# s2k_vr.net
KiCad netlist of a schematic drawn in EAGLE
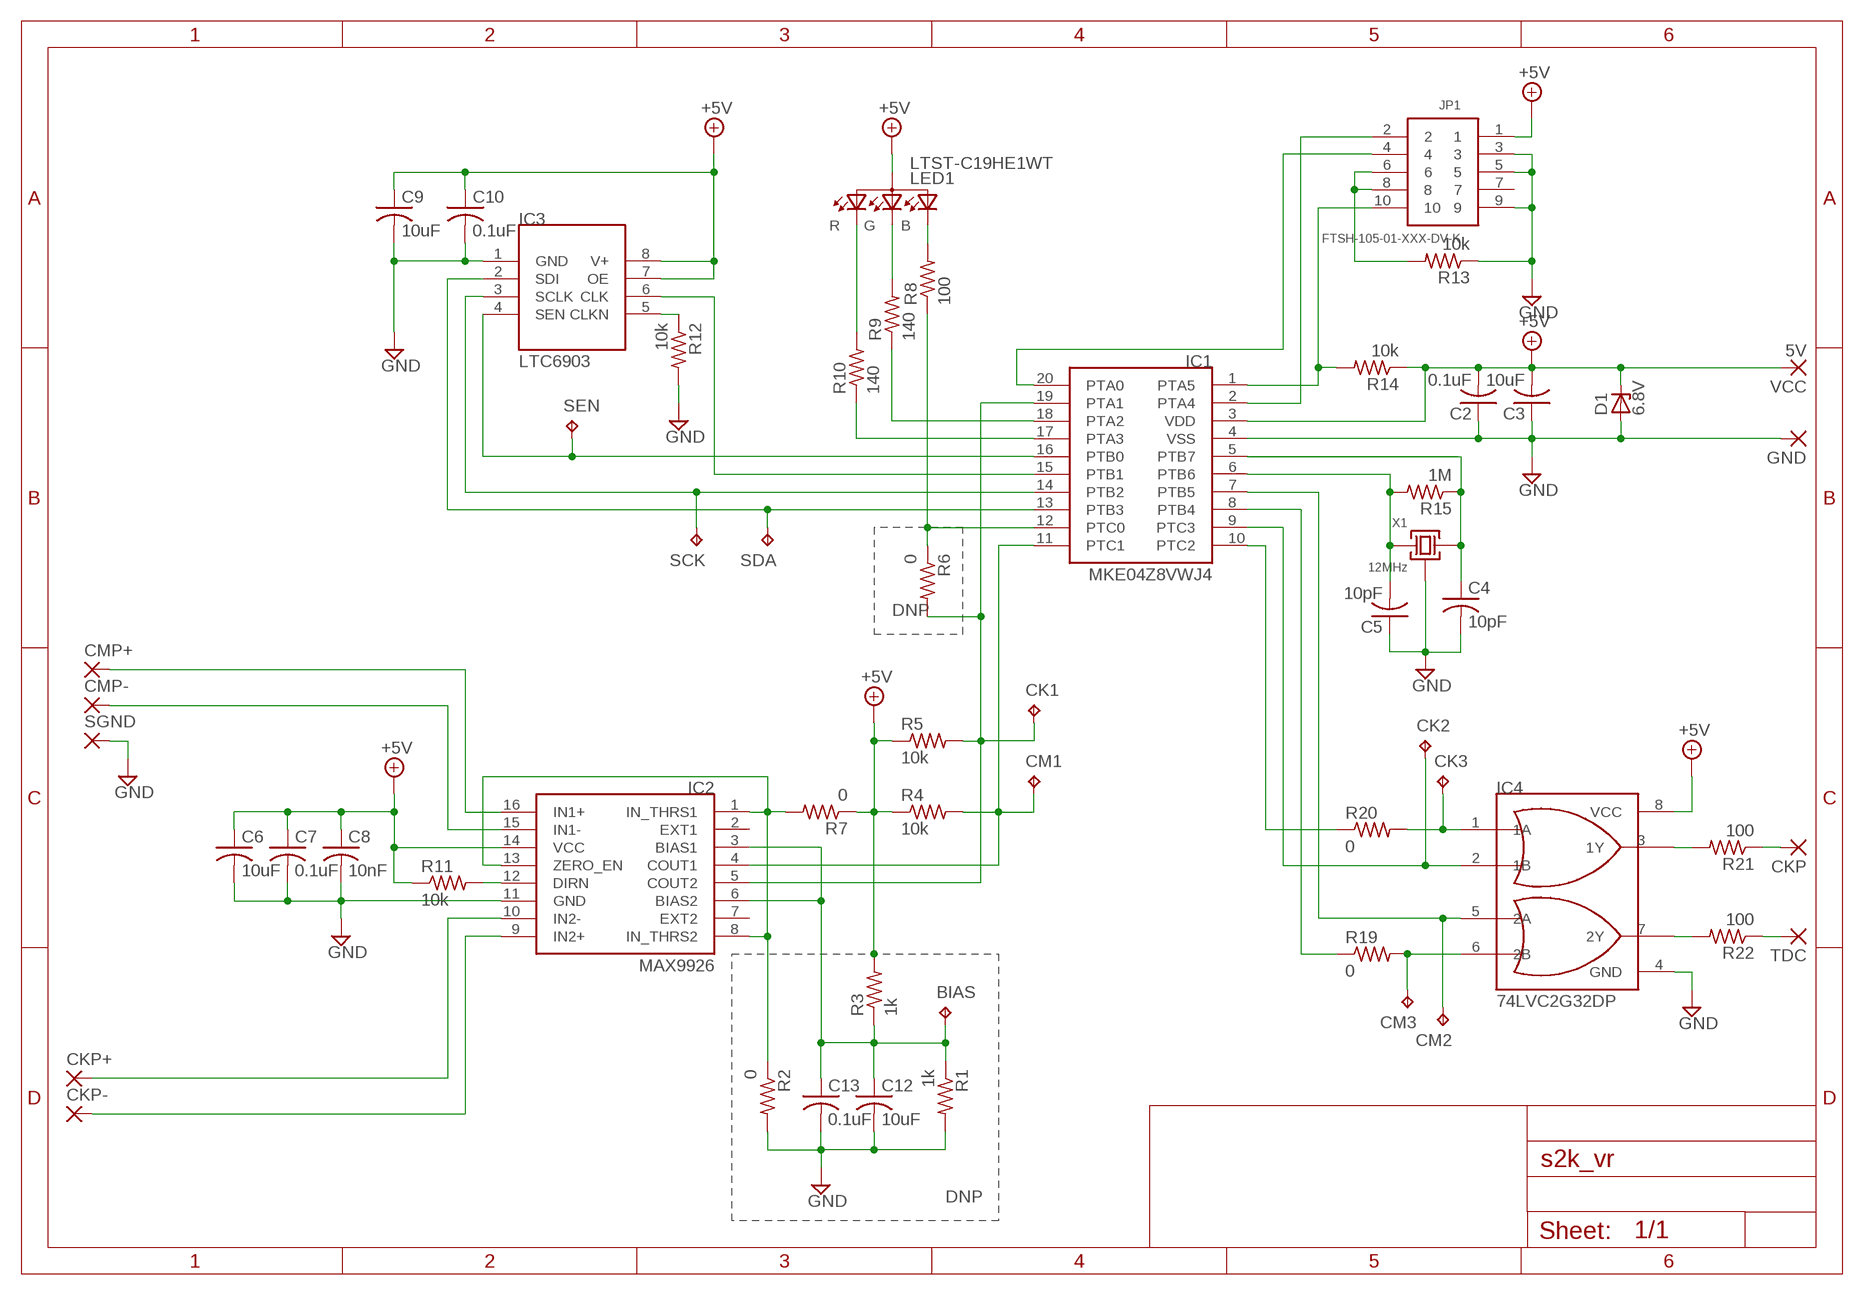
[diagram p0: schematic, sheet 1]

(export (version "E")
  (design (tool "Eeschema 10.0.6"))
  (components
    (comp (ref "BIAS")
      (value "TPB2,54")
      (footprint "eagle-import:B2,54")
      (libsource (lib "eagle-import") (part "TPB2,54"))
    )
    (comp (ref "C2")
      (value "0.1uF")
      (footprint "eagle-import:C0603")
      (libsource (lib "eagle-import") (part "C-USC0603"))
    )
    (comp (ref "C3")
      (value "10uF")
      (footprint "eagle-import:C0805")
      (libsource (lib "eagle-import") (part "C-USC0805"))
    )
    (comp (ref "C4")
      (value "10pF")
      (footprint "eagle-import:C0603")
      (libsource (lib "eagle-import") (part "C-USC0603"))
    )
    (comp (ref "C5")
      (value "10pF")
      (footprint "eagle-import:C0603")
      (libsource (lib "eagle-import") (part "C-USC0603"))
    )
    (comp (ref "C6")
      (value "10uF")
      (footprint "eagle-import:C0805")
      (libsource (lib "eagle-import") (part "C-USC0805"))
    )
    (comp (ref "C7")
      (value "0.1uF")
      (footprint "eagle-import:C0603")
      (libsource (lib "eagle-import") (part "C-USC0603"))
    )
    (comp (ref "C8")
      (value "10nF")
      (footprint "eagle-import:C0306")
      (libsource (lib "eagle-import") (part "CAP-0306"))
    )
    (comp (ref "C9")
      (value "10uF")
      (footprint "eagle-import:C0805")
      (libsource (lib "eagle-import") (part "C-USC0805"))
    )
    (comp (ref "C10")
      (value "0.1uF")
      (footprint "eagle-import:C0603")
      (libsource (lib "eagle-import") (part "C-USC0603"))
    )
    (comp (ref "C12")
      (value "10uF")
      (footprint "eagle-import:C0603")
      (libsource (lib "eagle-import") (part "C-USC0603"))
    )
    (comp (ref "C13")
      (value "0.1uF")
      (footprint "eagle-import:C0603")
      (libsource (lib "eagle-import") (part "C-USC0603"))
    )
    (comp (ref "CK1")
      (value "TPB2,54")
      (footprint "eagle-import:B2,54")
      (libsource (lib "eagle-import") (part "TPB2,54"))
    )
    (comp (ref "CK2")
      (value "TPB2,54")
      (footprint "eagle-import:B2,54")
      (libsource (lib "eagle-import") (part "TPB2,54"))
    )
    (comp (ref "CK3")
      (value "TPB2,54")
      (footprint "eagle-import:B2,54")
      (libsource (lib "eagle-import") (part "TPB2,54"))
    )
    (comp (ref "CKP")
      (value "3,81/1,4")
      (footprint "eagle-import:3,81_1,4")
      (libsource (lib "eagle-import") (part "3,81/1,4"))
    )
    (comp (ref "CKP+")
      (value "3,81/1,4")
      (footprint "eagle-import:3,81_1,4")
      (libsource (lib "eagle-import") (part "3,81/1,4"))
    )
    (comp (ref "CKP-")
      (value "3,81/1,4")
      (footprint "eagle-import:3,81_1,4")
      (libsource (lib "eagle-import") (part "3,81/1,4"))
    )
    (comp (ref "CM1")
      (value "TPB2,54")
      (footprint "eagle-import:B2,54")
      (libsource (lib "eagle-import") (part "TPB2,54"))
    )
    (comp (ref "CM2")
      (value "TPB2,54")
      (footprint "eagle-import:B2,54")
      (libsource (lib "eagle-import") (part "TPB2,54"))
    )
    (comp (ref "CM3")
      (value "TPB2,54")
      (footprint "eagle-import:B2,54")
      (libsource (lib "eagle-import") (part "TPB2,54"))
    )
    (comp (ref "CMP+")
      (value "3,81/1,4")
      (footprint "eagle-import:3,81_1,4")
      (libsource (lib "eagle-import") (part "3,81/1,4"))
    )
    (comp (ref "CMP-")
      (value "3,81/1,4")
      (footprint "eagle-import:3,81_1,4")
      (libsource (lib "eagle-import") (part "3,81/1,4"))
    )
    (comp (ref "D1")
      (value "6.8V")
      (footprint "eagle-import:SOT23")
      (libsource (lib "eagle-import") (part "ZENER-DIODESOT23"))
    )
    (comp (ref "GND")
      (value "3,81/1,4")
      (footprint "eagle-import:3,81_1,4")
      (libsource (lib "eagle-import") (part "3,81/1,4"))
    )
    (comp (ref "IC1")
      (value "MKE04Z8VWJ4")
      (footprint "eagle-import:SOIC20S")
      (libsource (lib "eagle-import") (part "MKE04Z8VWJ4"))
    )
    (comp (ref "IC2")
      (value "MAX9926")
      (footprint "eagle-import:16-QSOP")
      (libsource (lib "eagle-import") (part "MAX9926"))
    )
    (comp (ref "IC3")
      (value "LTC6903")
      (footprint "eagle-import:MS8")
      (libsource (lib "eagle-import") (part "LTC6903"))
    )
    (comp (ref "IC4")
      (value "74LVC2G32DP")
      (footprint "eagle-import:TSSOP8")
      (libsource (lib "eagle-import") (part "74LVC2G32DP"))
    )
    (comp (ref "JP1")
      (value "FTSH-105-01-XXX-DV-K")
      (footprint "eagle-import:FTSH-105-01-XXX-DV-K")
      (libsource (lib "eagle-import") (part "FTSH-105-01-XXX-DV-K"))
    )
    (comp (ref "LED1")
      (value "LTST-C19HE1WT")
      (footprint "eagle-import:LED-0606")
      (libsource (lib "eagle-import") (part "LTST-C19HE1WT"))
    )
    (comp (ref "R1")
      (value "1k")
      (footprint "eagle-import:R0603")
      (libsource (lib "eagle-import") (part "R-US_R0603"))
    )
    (comp (ref "R2")
      (value "0")
      (footprint "eagle-import:R0603")
      (libsource (lib "eagle-import") (part "R-US_R0603"))
    )
    (comp (ref "R3")
      (value "1k")
      (footprint "eagle-import:R0603")
      (libsource (lib "eagle-import") (part "R-US_R0603"))
    )
    (comp (ref "R4")
      (value "10k")
      (footprint "eagle-import:R0603")
      (libsource (lib "eagle-import") (part "R-US_R0603"))
    )
    (comp (ref "R5")
      (value "10k")
      (footprint "eagle-import:R0603")
      (libsource (lib "eagle-import") (part "R-US_R0603"))
    )
    (comp (ref "R6")
      (value "0")
      (footprint "eagle-import:R0603")
      (libsource (lib "eagle-import") (part "R-US_R0603"))
    )
    (comp (ref "R7")
      (value "0")
      (footprint "eagle-import:R0603")
      (libsource (lib "eagle-import") (part "R-US_R0603"))
    )
    (comp (ref "R8")
      (value "100")
      (footprint "eagle-import:R0603")
      (libsource (lib "eagle-import") (part "R-US_R0603"))
    )
    (comp (ref "R9")
      (value "140")
      (footprint "eagle-import:R0603")
      (libsource (lib "eagle-import") (part "R-US_R0603"))
    )
    (comp (ref "R10")
      (value "140")
      (footprint "eagle-import:R0603")
      (libsource (lib "eagle-import") (part "R-US_R0603"))
    )
    (comp (ref "R11")
      (value "10k")
      (footprint "eagle-import:R0603")
      (libsource (lib "eagle-import") (part "R-US_R0603"))
    )
    (comp (ref "R12")
      (value "10k")
      (footprint "eagle-import:R0603")
      (libsource (lib "eagle-import") (part "R-US_R0603"))
    )
    (comp (ref "R13")
      (value "10k")
      (footprint "eagle-import:R0603")
      (libsource (lib "eagle-import") (part "R-US_R0603"))
    )
    (comp (ref "R14")
      (value "10k")
      (footprint "eagle-import:R0603")
      (libsource (lib "eagle-import") (part "R-US_R0603"))
    )
    (comp (ref "R15")
      (value "1M")
      (footprint "eagle-import:R0603")
      (libsource (lib "eagle-import") (part "R-US_R0603"))
    )
    (comp (ref "R19")
      (value "0")
      (footprint "eagle-import:R0603")
      (libsource (lib "eagle-import") (part "R-US_R0603"))
    )
    (comp (ref "R20")
      (value "0")
      (footprint "eagle-import:R0603")
      (libsource (lib "eagle-import") (part "R-US_R0603"))
    )
    (comp (ref "R21")
      (value "100")
      (footprint "eagle-import:R0603")
      (libsource (lib "eagle-import") (part "R-US_R0603"))
    )
    (comp (ref "R22")
      (value "100")
      (footprint "eagle-import:R0603")
      (libsource (lib "eagle-import") (part "R-US_R0603"))
    )
    (comp (ref "SCK")
      (value "TPB2,54")
      (footprint "eagle-import:B2,54")
      (libsource (lib "eagle-import") (part "TPB2,54"))
    )
    (comp (ref "SDA")
      (value "TPB2,54")
      (footprint "eagle-import:B2,54")
      (libsource (lib "eagle-import") (part "TPB2,54"))
    )
    (comp (ref "SEN")
      (value "TPB2,54")
      (footprint "eagle-import:B2,54")
      (libsource (lib "eagle-import") (part "TPB2,54"))
    )
    (comp (ref "SGND")
      (value "3,81/1,4")
      (footprint "eagle-import:3,81_1,4")
      (libsource (lib "eagle-import") (part "3,81/1,4"))
    )
    (comp (ref "TDC")
      (value "3,81/1,4")
      (footprint "eagle-import:3,81_1,4")
      (libsource (lib "eagle-import") (part "3,81/1,4"))
    )
    (comp (ref "VCC")
      (value "5V")
      (footprint "eagle-import:3,81_1,4")
      (libsource (lib "eagle-import") (part "3,81/1,4"))
    )
    (comp (ref "X1")
      (value "12MHz")
      (footprint "eagle-import:SMD4-2520")
      (libsource (lib "eagle-import") (part "CX2520DB"))
    )
  )
  (nets
    (net (code "1") (name "+5V") (class "Default")
      (node (ref "C10") (pin "1") (pinfunction "1_1") (pintype "passive"))
      (node (ref "C2") (pin "2") (pinfunction "2_2") (pintype "passive"))
      (node (ref "C3") (pin "2") (pinfunction "2_2") (pintype "passive"))
      (node (ref "C6") (pin "1") (pinfunction "1_1") (pintype "passive"))
      (node (ref "C7") (pin "1") (pinfunction "1_1") (pintype "passive"))
      (node (ref "C8") (pin "1") (pinfunction "1_1") (pintype "passive"))
      (node (ref "C9") (pin "1") (pinfunction "1_1") (pintype "passive"))
      (node (ref "D1") (pin "3") (pinfunction "C_3") (pintype "passive"))
      (node (ref "IC1") (pin "3") (pinfunction "VDD_3") (pintype "bidirectional"))
      (node (ref "IC2") (pin "14") (pinfunction "VCC_14") (pintype "bidirectional"))
      (node (ref "IC3") (pin "7") (pinfunction "OE_7") (pintype "bidirectional"))
      (node (ref "IC3") (pin "8") (pinfunction "V+_8") (pintype "bidirectional"))
      (node (ref "IC4") (pin "8") (pinfunction "VCC_8") (pintype "bidirectional"))
      (node (ref "JP1") (pin "1") (pinfunction "1_1") (pintype "bidirectional"))
      (node (ref "LED1") (pin "4") (pinfunction "ANODE_4") (pintype "passive"))
      (node (ref "R11") (pin "1") (pinfunction "1_1") (pintype "passive"))
      (node (ref "R14") (pin "1") (pinfunction "1_1") (pintype "passive"))
      (node (ref "R3") (pin "2") (pinfunction "2_2") (pintype "passive"))
      (node (ref "R4") (pin "1") (pinfunction "1_1") (pintype "passive"))
      (node (ref "R5") (pin "1") (pinfunction "1_1") (pintype "passive"))
      (node (ref "R7") (pin "1") (pinfunction "1_1") (pintype "passive"))
      (node (ref "VCC") (pin "1") (pinfunction "P_1") (pintype "passive"))
    )
    (net (code "2") (name "GND") (class "Default")
      (node (ref "C10") (pin "2") (pinfunction "2_2") (pintype "passive"))
      (node (ref "C12") (pin "2") (pinfunction "2_2") (pintype "passive"))
      (node (ref "C13") (pin "2") (pinfunction "2_2") (pintype "passive"))
      (node (ref "C2") (pin "1") (pinfunction "1_1") (pintype "passive"))
      (node (ref "C3") (pin "1") (pinfunction "1_1") (pintype "passive"))
      (node (ref "C4") (pin "2") (pinfunction "2_2") (pintype "passive"))
      (node (ref "C5") (pin "1") (pinfunction "1_1") (pintype "passive"))
      (node (ref "C6") (pin "2") (pinfunction "2_2") (pintype "passive"))
      (node (ref "C7") (pin "2") (pinfunction "2_2") (pintype "passive"))
      (node (ref "C8") (pin "2") (pinfunction "2_2") (pintype "passive"))
      (node (ref "C9") (pin "2") (pinfunction "2_2") (pintype "passive"))
      (node (ref "D1") (pin "1") (pinfunction "A_1") (pintype "passive"))
      (node (ref "GND") (pin "1") (pinfunction "P_1") (pintype "passive"))
      (node (ref "IC1") (pin "4") (pinfunction "VSS_4") (pintype "bidirectional"))
      (node (ref "IC2") (pin "11") (pinfunction "GND_11") (pintype "bidirectional"))
      (node (ref "IC3") (pin "1") (pinfunction "GND_1") (pintype "bidirectional"))
      (node (ref "IC4") (pin "4") (pinfunction "GND_4") (pintype "bidirectional"))
      (node (ref "JP1") (pin "3") (pinfunction "3_3") (pintype "bidirectional"))
      (node (ref "JP1") (pin "5") (pinfunction "5_5") (pintype "bidirectional"))
      (node (ref "JP1") (pin "9") (pinfunction "9_9") (pintype "bidirectional"))
      (node (ref "R1") (pin "2") (pinfunction "2_2") (pintype "passive"))
      (node (ref "R12") (pin "2") (pinfunction "2_2") (pintype "passive"))
      (node (ref "R13") (pin "1") (pinfunction "1_1") (pintype "passive"))
      (node (ref "R2") (pin "2") (pinfunction "2_2") (pintype "passive"))
      (node (ref "SGND") (pin "1") (pinfunction "P_1") (pintype "passive"))
      (node (ref "X1") (pin "2") (pinfunction "GND_2") (pintype "bidirectional"))
      (node (ref "X1") (pin "4") (pinfunction "GND_4") (pintype "bidirectional"))
    )
    (net (code "3") (name "Net-(CKP+-P)") (class "Default")
      (node (ref "CKP+") (pin "1") (pinfunction "P_1") (pintype "passive"))
      (node (ref "IC2") (pin "10") (pinfunction "IN2-_10") (pintype "bidirectional"))
    )
    (net (code "4") (name "Net-(CKP--P)") (class "Default")
      (node (ref "CKP-") (pin "1") (pinfunction "P_1") (pintype "passive"))
      (node (ref "IC2") (pin "9") (pinfunction "IN2+_9") (pintype "bidirectional"))
    )
    (net (code "5") (name "Net-(CKP-P)") (class "Default")
      (node (ref "CKP") (pin "1") (pinfunction "P_1") (pintype "passive"))
      (node (ref "R21") (pin "1") (pinfunction "1_1") (pintype "passive"))
    )
    (net (code "6") (name "Net-(CMP+-P)") (class "Default")
      (node (ref "CMP+") (pin "1") (pinfunction "P_1") (pintype "passive"))
      (node (ref "IC2") (pin "16") (pinfunction "IN1+_16") (pintype "bidirectional"))
    )
    (net (code "7") (name "Net-(CMP--P)") (class "Default")
      (node (ref "CMP-") (pin "1") (pinfunction "P_1") (pintype "passive"))
      (node (ref "IC2") (pin "15") (pinfunction "IN1-_15") (pintype "bidirectional"))
    )
    (net (code "8") (name "Net-(IC1-PTA0)") (class "Default")
      (node (ref "IC1") (pin "20") (pinfunction "PTA0_20") (pintype "bidirectional"))
      (node (ref "JP1") (pin "4") (pinfunction "4_4") (pintype "bidirectional"))
    )
    (net (code "9") (name "Net-(IC1-PTA1)") (class "Default")
      (node (ref "CK1") (pin "TP") (pinfunction "TP_TP") (pintype "input"))
      (node (ref "IC1") (pin "19") (pinfunction "PTA1_19") (pintype "bidirectional"))
      (node (ref "IC2") (pin "5") (pinfunction "COUT2_5") (pintype "bidirectional"))
      (node (ref "R5") (pin "2") (pinfunction "2_2") (pintype "passive"))
      (node (ref "R6") (pin "2") (pinfunction "2_2") (pintype "passive"))
    )
    (net (code "10") (name "Net-(IC1-PTA2)") (class "Default")
      (node (ref "IC1") (pin "18") (pinfunction "PTA2_18") (pintype "bidirectional"))
      (node (ref "R9") (pin "1") (pinfunction "1_1") (pintype "passive"))
    )
    (net (code "11") (name "Net-(IC1-PTA3)") (class "Default")
      (node (ref "IC1") (pin "17") (pinfunction "PTA3_17") (pintype "bidirectional"))
      (node (ref "R10") (pin "1") (pinfunction "1_1") (pintype "passive"))
    )
    (net (code "12") (name "Net-(IC1-PTA4)") (class "Default")
      (node (ref "IC1") (pin "2") (pinfunction "PTA4_2") (pintype "bidirectional"))
      (node (ref "JP1") (pin "2") (pinfunction "2_2") (pintype "bidirectional"))
    )
    (net (code "13") (name "Net-(IC1-PTA5)") (class "Default")
      (node (ref "IC1") (pin "1") (pinfunction "PTA5_1") (pintype "bidirectional"))
      (node (ref "JP1") (pin "10") (pinfunction "10_10") (pintype "bidirectional"))
      (node (ref "R14") (pin "2") (pinfunction "2_2") (pintype "passive"))
    )
    (net (code "14") (name "Net-(IC1-PTB0)") (class "Default")
      (node (ref "IC1") (pin "16") (pinfunction "PTB0_16") (pintype "bidirectional"))
      (node (ref "IC3") (pin "4") (pinfunction "SEN_4") (pintype "bidirectional"))
      (node (ref "SEN") (pin "TP") (pinfunction "TP_TP") (pintype "input"))
    )
    (net (code "15") (name "Net-(IC1-PTB1)") (class "Default")
      (node (ref "IC1") (pin "15") (pinfunction "PTB1_15") (pintype "bidirectional"))
      (node (ref "IC3") (pin "6") (pinfunction "CLK_6") (pintype "bidirectional"))
    )
    (net (code "16") (name "Net-(IC1-PTB2)") (class "Default")
      (node (ref "IC1") (pin "14") (pinfunction "PTB2_14") (pintype "bidirectional"))
      (node (ref "IC3") (pin "3") (pinfunction "SCLK_3") (pintype "bidirectional"))
      (node (ref "SCK") (pin "TP") (pinfunction "TP_TP") (pintype "input"))
    )
    (net (code "17") (name "Net-(IC1-PTB3)") (class "Default")
      (node (ref "IC1") (pin "13") (pinfunction "PTB3_13") (pintype "bidirectional"))
      (node (ref "IC3") (pin "2") (pinfunction "SDI_2") (pintype "bidirectional"))
      (node (ref "SDA") (pin "TP") (pinfunction "TP_TP") (pintype "input"))
    )
    (net (code "18") (name "Net-(IC1-PTB4)") (class "Default")
      (node (ref "IC1") (pin "8") (pinfunction "PTB4_8") (pintype "bidirectional"))
      (node (ref "R19") (pin "1") (pinfunction "1_1") (pintype "passive"))
    )
    (net (code "19") (name "Net-(IC1-PTB5)") (class "Default")
      (node (ref "CM2") (pin "TP") (pinfunction "TP_TP") (pintype "input"))
      (node (ref "IC1") (pin "7") (pinfunction "PTB5_7") (pintype "bidirectional"))
      (node (ref "IC4") (pin "5") (pinfunction "2A_5") (pintype "bidirectional"))
    )
    (net (code "20") (name "Net-(IC1-PTB6)") (class "Default")
      (node (ref "C5") (pin "2") (pinfunction "2_2") (pintype "passive"))
      (node (ref "IC1") (pin "6") (pinfunction "PTB6_6") (pintype "bidirectional"))
      (node (ref "R15") (pin "2") (pinfunction "2_2") (pintype "passive"))
      (node (ref "X1") (pin "3") (pinfunction "2_3") (pintype "bidirectional"))
    )
    (net (code "21") (name "Net-(IC1-PTB7)") (class "Default")
      (node (ref "C4") (pin "1") (pinfunction "1_1") (pintype "passive"))
      (node (ref "IC1") (pin "5") (pinfunction "PTB7_5") (pintype "bidirectional"))
      (node (ref "R15") (pin "1") (pinfunction "1_1") (pintype "passive"))
      (node (ref "X1") (pin "1") (pinfunction "1_1") (pintype "bidirectional"))
    )
    (net (code "22") (name "Net-(IC1-PTC0)") (class "Default")
      (node (ref "IC1") (pin "12") (pinfunction "PTC0_12") (pintype "bidirectional"))
      (node (ref "R6") (pin "1") (pinfunction "1_1") (pintype "passive"))
      (node (ref "R8") (pin "1") (pinfunction "1_1") (pintype "passive"))
    )
    (net (code "23") (name "Net-(IC1-PTC1)") (class "Default")
      (node (ref "CM1") (pin "TP") (pinfunction "TP_TP") (pintype "input"))
      (node (ref "IC1") (pin "11") (pinfunction "PTC1_11") (pintype "bidirectional"))
      (node (ref "IC2") (pin "4") (pinfunction "COUT1_4") (pintype "bidirectional"))
      (node (ref "R4") (pin "2") (pinfunction "2_2") (pintype "passive"))
    )
    (net (code "24") (name "Net-(IC1-PTC2)") (class "Default")
      (node (ref "IC1") (pin "10") (pinfunction "PTC2_10") (pintype "bidirectional"))
      (node (ref "R20") (pin "1") (pinfunction "1_1") (pintype "passive"))
    )
    (net (code "25") (name "Net-(IC1-PTC3)") (class "Default")
      (node (ref "CK2") (pin "TP") (pinfunction "TP_TP") (pintype "input"))
      (node (ref "IC1") (pin "9") (pinfunction "PTC3_9") (pintype "bidirectional"))
      (node (ref "IC4") (pin "2") (pinfunction "1B_2") (pintype "bidirectional"))
    )
    (net (code "26") (name "Net-(IC2-BIAS1)") (class "Default")
      (node (ref "BIAS") (pin "TP") (pinfunction "TP_TP") (pintype "input"))
      (node (ref "C12") (pin "1") (pinfunction "1_1") (pintype "passive"))
      (node (ref "C13") (pin "1") (pinfunction "1_1") (pintype "passive"))
      (node (ref "IC2") (pin "3") (pinfunction "BIAS1_3") (pintype "bidirectional"))
      (node (ref "IC2") (pin "6") (pinfunction "BIAS2_6") (pintype "bidirectional"))
      (node (ref "R1") (pin "1") (pinfunction "1_1") (pintype "passive"))
      (node (ref "R3") (pin "1") (pinfunction "1_1") (pintype "passive"))
    )
    (net (code "27") (name "Net-(IC2-DIRN)") (class "Default")
      (node (ref "IC2") (pin "12") (pinfunction "DIRN_12") (pintype "bidirectional"))
      (node (ref "R11") (pin "2") (pinfunction "2_2") (pintype "passive"))
    )
    (net (code "28") (name "Net-(IC2-IN_THRS1)") (class "Default")
      (node (ref "IC2") (pin "1") (pinfunction "IN_THRS1_1") (pintype "bidirectional"))
      (node (ref "IC2") (pin "13") (pinfunction "ZERO_EN_13") (pintype "bidirectional"))
      (node (ref "IC2") (pin "8") (pinfunction "IN_THRS2_8") (pintype "bidirectional"))
      (node (ref "R2") (pin "1") (pinfunction "1_1") (pintype "passive"))
      (node (ref "R7") (pin "2") (pinfunction "2_2") (pintype "passive"))
    )
    (net (code "29") (name "Net-(IC3-CLKN)") (class "Default")
      (node (ref "IC3") (pin "5") (pinfunction "CLKN_5") (pintype "bidirectional"))
      (node (ref "R12") (pin "1") (pinfunction "1_1") (pintype "passive"))
    )
    (net (code "30") (name "Net-(IC4-1A)") (class "Default")
      (node (ref "CK3") (pin "TP") (pinfunction "TP_TP") (pintype "input"))
      (node (ref "IC4") (pin "1") (pinfunction "1A_1") (pintype "bidirectional"))
      (node (ref "R20") (pin "2") (pinfunction "2_2") (pintype "passive"))
    )
    (net (code "31") (name "Net-(IC4-1Y)") (class "Default")
      (node (ref "IC4") (pin "3") (pinfunction "1Y_3") (pintype "bidirectional"))
      (node (ref "R21") (pin "2") (pinfunction "2_2") (pintype "passive"))
    )
    (net (code "32") (name "Net-(IC4-2B)") (class "Default")
      (node (ref "CM3") (pin "TP") (pinfunction "TP_TP") (pintype "input"))
      (node (ref "IC4") (pin "6") (pinfunction "2B_6") (pintype "bidirectional"))
      (node (ref "R19") (pin "2") (pinfunction "2_2") (pintype "passive"))
    )
    (net (code "33") (name "Net-(IC4-2Y)") (class "Default")
      (node (ref "IC4") (pin "7") (pinfunction "2Y_7") (pintype "bidirectional"))
      (node (ref "R22") (pin "2") (pinfunction "2_2") (pintype "passive"))
    )
    (net (code "34") (name "Net-(JP1-Pad6)") (class "Default")
      (node (ref "JP1") (pin "6") (pinfunction "6_6") (pintype "bidirectional"))
      (node (ref "JP1") (pin "8") (pinfunction "8_8") (pintype "bidirectional"))
      (node (ref "R13") (pin "2") (pinfunction "2_2") (pintype "passive"))
    )
    (net (code "35") (name "Net-(LED1-B)") (class "Default")
      (node (ref "LED1") (pin "3") (pinfunction "B_3") (pintype "passive"))
      (node (ref "R8") (pin "2") (pinfunction "2_2") (pintype "passive"))
    )
    (net (code "36") (name "Net-(LED1-G)") (class "Default")
      (node (ref "LED1") (pin "2") (pinfunction "G_2") (pintype "passive"))
      (node (ref "R9") (pin "2") (pinfunction "2_2") (pintype "passive"))
    )
    (net (code "37") (name "Net-(LED1-R)") (class "Default")
      (node (ref "LED1") (pin "1") (pinfunction "R_1") (pintype "passive"))
      (node (ref "R10") (pin "2") (pinfunction "2_2") (pintype "passive"))
    )
    (net (code "38") (name "Net-(TDC-P)") (class "Default")
      (node (ref "R22") (pin "1") (pinfunction "1_1") (pintype "passive"))
      (node (ref "TDC") (pin "1") (pinfunction "P_1") (pintype "passive"))
    )
    (net (code "39") (name "unconnected-(IC2-EXT1-Pad2)") (class "Default")
      (node (ref "IC2") (pin "2") (pinfunction "EXT1_2") (pintype "bidirectional"))
    )
    (net (code "40") (name "unconnected-(IC2-EXT2-Pad7)") (class "Default")
      (node (ref "IC2") (pin "7") (pinfunction "EXT2_7") (pintype "bidirectional"))
    )
    (net (code "41") (name "unconnected-(JP1-Pad7)") (class "Default")
      (node (ref "JP1") (pin "7") (pinfunction "7_7") (pintype "bidirectional"))
    )
  )
)
